# SPI_Interface.net
KiCad netlist of a schematic drawn in Altium Designer
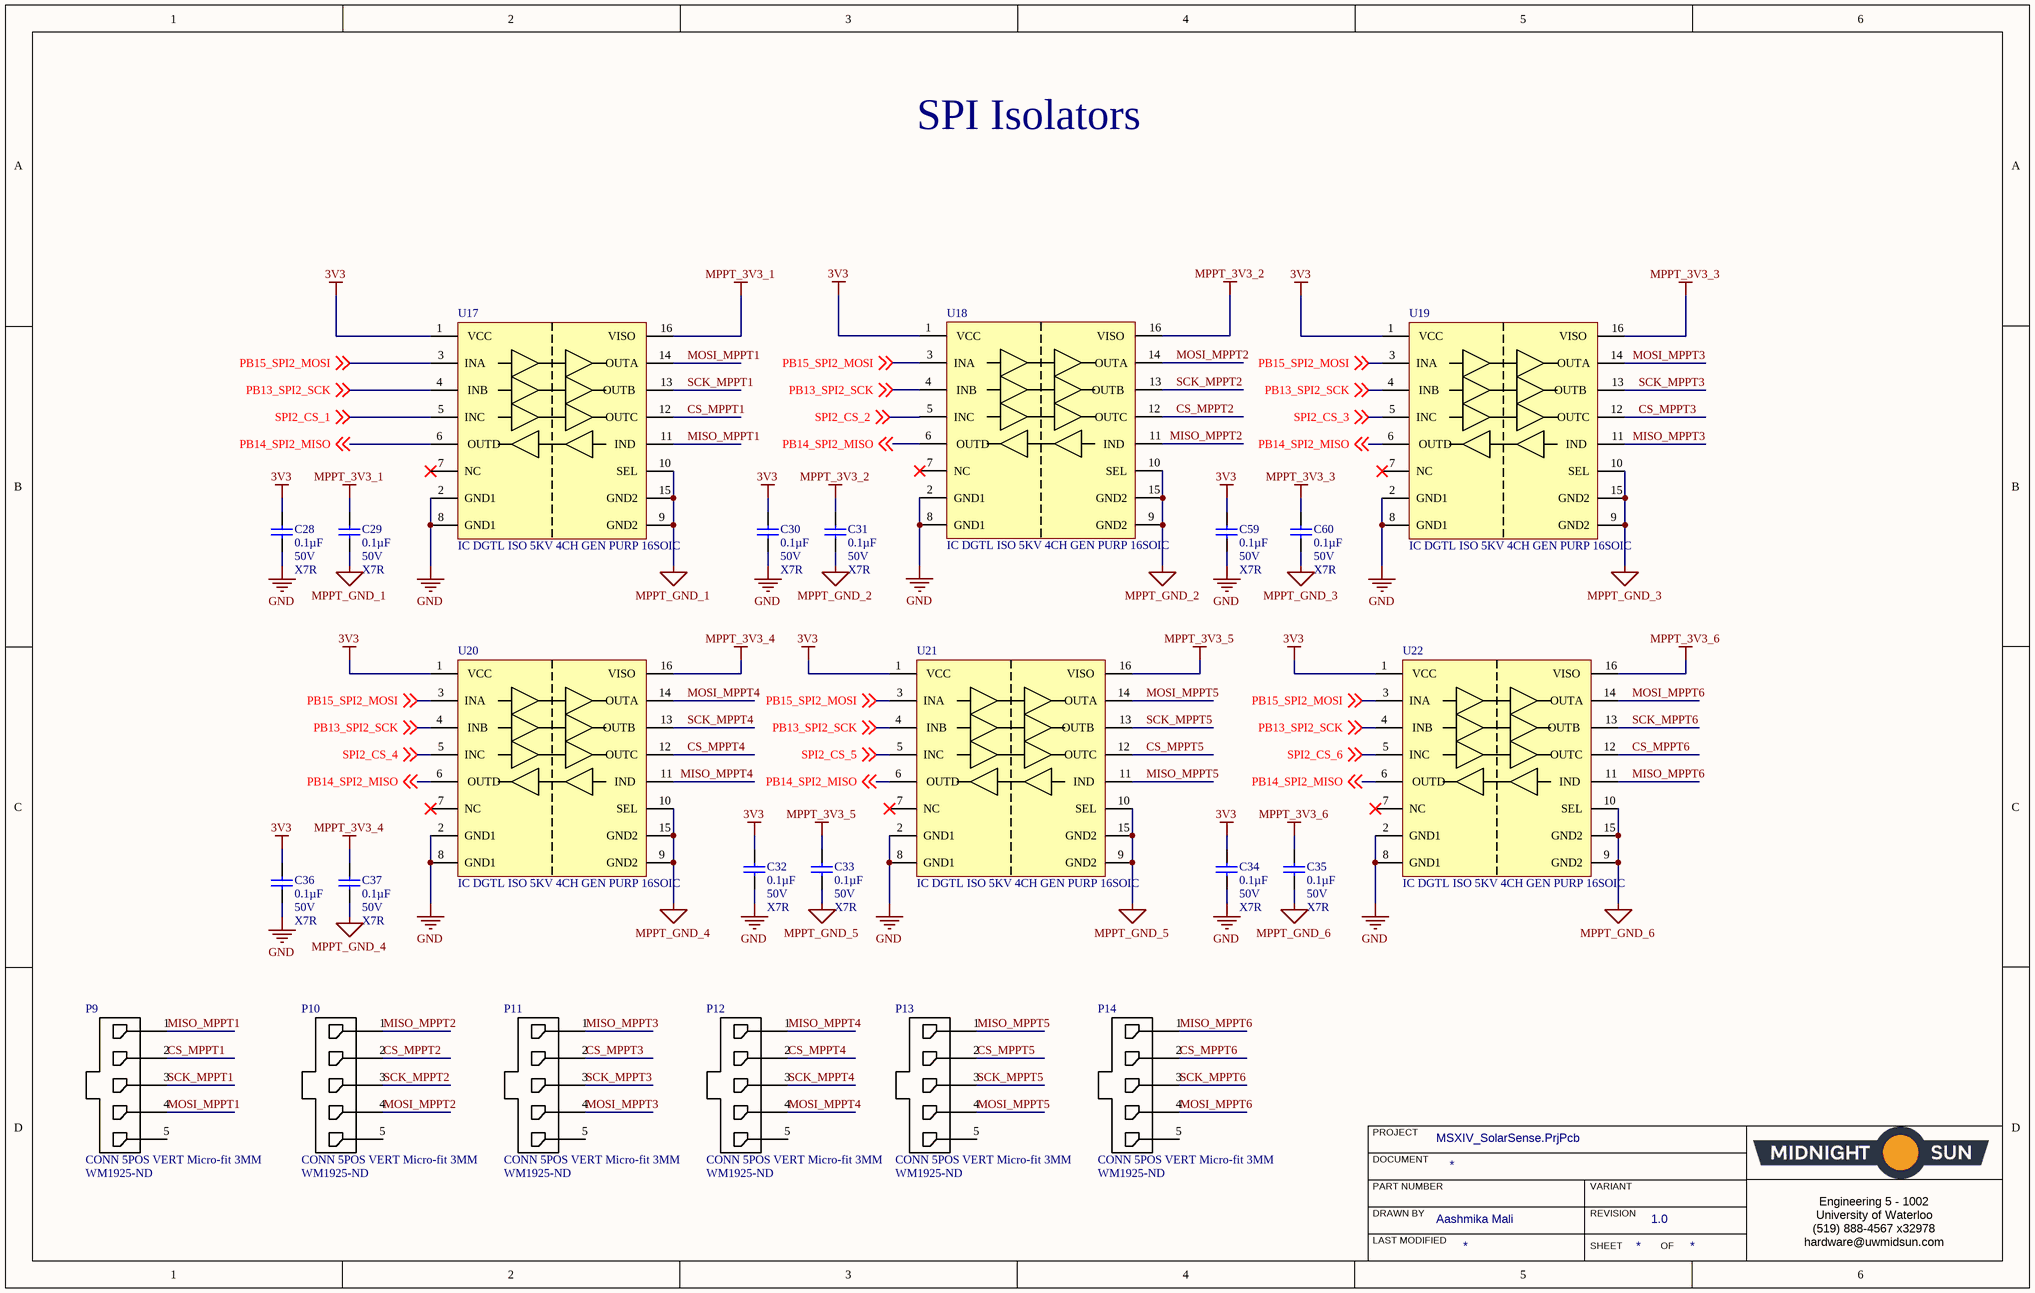
[diagram p0: SPI_Interface.SchDoc]

(export (version "E")
  (design (tool "Eeschema 10.0.6"))
  (components
    (comp (ref "C28")
      (value "CAP CER 0.1UF 50V 10% X7R 0603")
      (footprint "CAP, 0603")
      (description "0.10µF ±10% 50V Ceramic Capacitor X7R 0603 (1608 Metric)")
      (fields
        (field (name "TOLERANCE") "±10%")
        (field (name "CAPACITANCE") "0.1µF")
        (field (name "VOLTAGE") "50V")
        (field (name "TEMPERATURE COEFFICIENT") "X7R")
      )
      (libsource (lib "Schematic Diagrams") (part "CAP CER 0.1UF 50V 10% X7R 0603"))
    )
    (comp (ref "C29")
      (value "CAP CER 0.1UF 50V 10% X7R 0603")
      (footprint "CAP, 0603")
      (description "0.10µF ±10% 50V Ceramic Capacitor X7R 0603 (1608 Metric)")
      (fields
        (field (name "TOLERANCE") "±10%")
        (field (name "CAPACITANCE") "0.1µF")
        (field (name "VOLTAGE") "50V")
        (field (name "TEMPERATURE COEFFICIENT") "X7R")
      )
      (libsource (lib "Schematic Diagrams") (part "CAP CER 0.1UF 50V 10% X7R 0603"))
    )
    (comp (ref "C30")
      (value "CAP CER 0.1UF 50V 10% X7R 0603")
      (footprint "CAP, 0603")
      (description "0.10µF ±10% 50V Ceramic Capacitor X7R 0603 (1608 Metric)")
      (fields
        (field (name "TOLERANCE") "±10%")
        (field (name "CAPACITANCE") "0.1µF")
        (field (name "VOLTAGE") "50V")
        (field (name "TEMPERATURE COEFFICIENT") "X7R")
      )
      (libsource (lib "Schematic Diagrams") (part "CAP CER 0.1UF 50V 10% X7R 0603"))
    )
    (comp (ref "C31")
      (value "CAP CER 0.1UF 50V 10% X7R 0603")
      (footprint "CAP, 0603")
      (description "0.10µF ±10% 50V Ceramic Capacitor X7R 0603 (1608 Metric)")
      (fields
        (field (name "TOLERANCE") "±10%")
        (field (name "CAPACITANCE") "0.1µF")
        (field (name "VOLTAGE") "50V")
        (field (name "TEMPERATURE COEFFICIENT") "X7R")
      )
      (libsource (lib "Schematic Diagrams") (part "CAP CER 0.1UF 50V 10% X7R 0603"))
    )
    (comp (ref "C32")
      (value "CAP CER 0.1UF 50V 10% X7R 0603")
      (footprint "CAP, 0603")
      (description "0.10µF ±10% 50V Ceramic Capacitor X7R 0603 (1608 Metric)")
      (fields
        (field (name "TOLERANCE") "±10%")
        (field (name "CAPACITANCE") "0.1µF")
        (field (name "VOLTAGE") "50V")
        (field (name "TEMPERATURE COEFFICIENT") "X7R")
      )
      (libsource (lib "Schematic Diagrams") (part "CAP CER 0.1UF 50V 10% X7R 0603"))
    )
    (comp (ref "C33")
      (value "CAP CER 0.1UF 50V 10% X7R 0603")
      (footprint "CAP, 0603")
      (description "0.10µF ±10% 50V Ceramic Capacitor X7R 0603 (1608 Metric)")
      (fields
        (field (name "TOLERANCE") "±10%")
        (field (name "CAPACITANCE") "0.1µF")
        (field (name "VOLTAGE") "50V")
        (field (name "TEMPERATURE COEFFICIENT") "X7R")
      )
      (libsource (lib "Schematic Diagrams") (part "CAP CER 0.1UF 50V 10% X7R 0603"))
    )
    (comp (ref "C34")
      (value "CAP CER 0.1UF 50V 10% X7R 0603")
      (footprint "CAP, 0603")
      (description "0.10µF ±10% 50V Ceramic Capacitor X7R 0603 (1608 Metric)")
      (fields
        (field (name "TOLERANCE") "±10%")
        (field (name "CAPACITANCE") "0.1µF")
        (field (name "VOLTAGE") "50V")
        (field (name "TEMPERATURE COEFFICIENT") "X7R")
      )
      (libsource (lib "Schematic Diagrams") (part "CAP CER 0.1UF 50V 10% X7R 0603"))
    )
    (comp (ref "C35")
      (value "CAP CER 0.1UF 50V 10% X7R 0603")
      (footprint "CAP, 0603")
      (description "0.10µF ±10% 50V Ceramic Capacitor X7R 0603 (1608 Metric)")
      (fields
        (field (name "TOLERANCE") "±10%")
        (field (name "CAPACITANCE") "0.1µF")
        (field (name "VOLTAGE") "50V")
        (field (name "TEMPERATURE COEFFICIENT") "X7R")
      )
      (libsource (lib "Schematic Diagrams") (part "CAP CER 0.1UF 50V 10% X7R 0603"))
    )
    (comp (ref "C36")
      (value "CAP CER 0.1UF 50V 10% X7R 0603")
      (footprint "CAP, 0603")
      (description "0.10µF ±10% 50V Ceramic Capacitor X7R 0603 (1608 Metric)")
      (fields
        (field (name "TOLERANCE") "±10%")
        (field (name "CAPACITANCE") "0.1µF")
        (field (name "VOLTAGE") "50V")
        (field (name "TEMPERATURE COEFFICIENT") "X7R")
      )
      (libsource (lib "Schematic Diagrams") (part "CAP CER 0.1UF 50V 10% X7R 0603"))
    )
    (comp (ref "C37")
      (value "CAP CER 0.1UF 50V 10% X7R 0603")
      (footprint "CAP, 0603")
      (description "0.10µF ±10% 50V Ceramic Capacitor X7R 0603 (1608 Metric)")
      (fields
        (field (name "TOLERANCE") "±10%")
        (field (name "CAPACITANCE") "0.1µF")
        (field (name "VOLTAGE") "50V")
        (field (name "TEMPERATURE COEFFICIENT") "X7R")
      )
      (libsource (lib "Schematic Diagrams") (part "CAP CER 0.1UF 50V 10% X7R 0603"))
    )
    (comp (ref "C59")
      (value "CAP CER 0.1UF 50V 10% X7R 0603")
      (footprint "CAP, 0603")
      (description "0.10µF ±10% 50V Ceramic Capacitor X7R 0603 (1608 Metric)")
      (fields
        (field (name "TOLERANCE") "±10%")
        (field (name "CAPACITANCE") "0.1µF")
        (field (name "VOLTAGE") "50V")
        (field (name "TEMPERATURE COEFFICIENT") "X7R")
      )
      (libsource (lib "Schematic Diagrams") (part "CAP CER 0.1UF 50V 10% X7R 0603"))
    )
    (comp (ref "C60")
      (value "CAP CER 0.1UF 50V 10% X7R 0603")
      (footprint "CAP, 0603")
      (description "0.10µF ±10% 50V Ceramic Capacitor X7R 0603 (1608 Metric)")
      (fields
        (field (name "TOLERANCE") "±10%")
        (field (name "CAPACITANCE") "0.1µF")
        (field (name "VOLTAGE") "50V")
        (field (name "TEMPERATURE COEFFICIENT") "X7R")
      )
      (libsource (lib "Schematic Diagrams") (part "CAP CER 0.1UF 50V 10% X7R 0603"))
    )
    (comp (ref "P9")
      (value "CONN 5POS VERT Micro-fit 3MM")
      (footprint "CONN, 5POS MICRO-FIT 3mm")
      (description "Conn Power HDR 5 POS 3mm Solder ST Thru-Hole 5 Terminal 1 Port Micro-Fit 3.0™ Tray")
      (fields
        (field (name "MANUFACTURER") "Molex")
        (field (name "MANUFACTURER PART NUMBER") "0436500516")
        (field (name "SUPPLIER PART NUMBER 1") "WM1925-ND")
      )
      (libsource (lib "Schematic Diagrams") (part "CONN 5POS VERT Micro-fit 3MM"))
    )
    (comp (ref "P10")
      (value "CONN 5POS VERT Micro-fit 3MM")
      (footprint "CONN, 5POS MICRO-FIT 3mm")
      (description "Conn Power HDR 5 POS 3mm Solder ST Thru-Hole 5 Terminal 1 Port Micro-Fit 3.0™ Tray")
      (fields
        (field (name "MANUFACTURER") "Molex")
        (field (name "MANUFACTURER PART NUMBER") "0436500516")
        (field (name "SUPPLIER PART NUMBER 1") "WM1925-ND")
      )
      (libsource (lib "Schematic Diagrams") (part "CONN 5POS VERT Micro-fit 3MM"))
    )
    (comp (ref "P11")
      (value "CONN 5POS VERT Micro-fit 3MM")
      (footprint "CONN, 5POS MICRO-FIT 3mm")
      (description "Conn Power HDR 5 POS 3mm Solder ST Thru-Hole 5 Terminal 1 Port Micro-Fit 3.0™ Tray")
      (fields
        (field (name "MANUFACTURER") "Molex")
        (field (name "MANUFACTURER PART NUMBER") "0436500516")
        (field (name "SUPPLIER PART NUMBER 1") "WM1925-ND")
      )
      (libsource (lib "Schematic Diagrams") (part "CONN 5POS VERT Micro-fit 3MM"))
    )
    (comp (ref "P12")
      (value "CONN 5POS VERT Micro-fit 3MM")
      (footprint "CONN, 5POS MICRO-FIT 3mm")
      (description "Conn Power HDR 5 POS 3mm Solder ST Thru-Hole 5 Terminal 1 Port Micro-Fit 3.0™ Tray")
      (fields
        (field (name "MANUFACTURER") "Molex")
        (field (name "MANUFACTURER PART NUMBER") "0436500516")
        (field (name "SUPPLIER PART NUMBER 1") "WM1925-ND")
      )
      (libsource (lib "Schematic Diagrams") (part "CONN 5POS VERT Micro-fit 3MM"))
    )
    (comp (ref "P13")
      (value "CONN 5POS VERT Micro-fit 3MM")
      (footprint "CONN, 5POS MICRO-FIT 3mm")
      (description "Conn Power HDR 5 POS 3mm Solder ST Thru-Hole 5 Terminal 1 Port Micro-Fit 3.0™ Tray")
      (fields
        (field (name "MANUFACTURER") "Molex")
        (field (name "MANUFACTURER PART NUMBER") "0436500516")
        (field (name "SUPPLIER PART NUMBER 1") "WM1925-ND")
      )
      (libsource (lib "Schematic Diagrams") (part "CONN 5POS VERT Micro-fit 3MM"))
    )
    (comp (ref "P14")
      (value "CONN 5POS VERT Micro-fit 3MM")
      (footprint "CONN, 5POS MICRO-FIT 3mm")
      (description "Conn Power HDR 5 POS 3mm Solder ST Thru-Hole 5 Terminal 1 Port Micro-Fit 3.0™ Tray")
      (fields
        (field (name "MANUFACTURER") "Molex")
        (field (name "MANUFACTURER PART NUMBER") "0436500516")
        (field (name "SUPPLIER PART NUMBER 1") "WM1925-ND")
      )
      (libsource (lib "Schematic Diagrams") (part "CONN 5POS VERT Micro-fit 3MM"))
    )
    (comp (ref "U17")
      (value "IC DGTL ISO 5KV 4CH GEN PURP 16SOIC")
      (footprint "ISOW7841FDWER SOIC-16")
      (libsource (lib "Schematic Diagrams") (part "IC DGTL ISO 5KV 4CH GEN PURP 16SOIC"))
    )
    (comp (ref "U18")
      (value "IC DGTL ISO 5KV 4CH GEN PURP 16SOIC")
      (footprint "ISOW7841FDWER SOIC-16")
      (libsource (lib "Schematic Diagrams") (part "IC DGTL ISO 5KV 4CH GEN PURP 16SOIC"))
    )
    (comp (ref "U19")
      (value "IC DGTL ISO 5KV 4CH GEN PURP 16SOIC")
      (footprint "ISOW7841FDWER SOIC-16")
      (libsource (lib "Schematic Diagrams") (part "IC DGTL ISO 5KV 4CH GEN PURP 16SOIC"))
    )
    (comp (ref "U20")
      (value "IC DGTL ISO 5KV 4CH GEN PURP 16SOIC")
      (footprint "ISOW7841FDWER SOIC-16")
      (libsource (lib "Schematic Diagrams") (part "IC DGTL ISO 5KV 4CH GEN PURP 16SOIC"))
    )
    (comp (ref "U21")
      (value "IC DGTL ISO 5KV 4CH GEN PURP 16SOIC")
      (footprint "ISOW7841FDWER SOIC-16")
      (libsource (lib "Schematic Diagrams") (part "IC DGTL ISO 5KV 4CH GEN PURP 16SOIC"))
    )
    (comp (ref "U22")
      (value "IC DGTL ISO 5KV 4CH GEN PURP 16SOIC")
      (footprint "ISOW7841FDWER SOIC-16")
      (libsource (lib "Schematic Diagrams") (part "IC DGTL ISO 5KV 4CH GEN PURP 16SOIC"))
    )
  )
  (nets
    (net (code "1") (name "/CS_MPPT1") (class "Default")
      (node (ref "P9") (pin "2") (pinfunction "2_2") (pintype "passive"))
      (node (ref "U17") (pin "12") (pinfunction "OUTC_12") (pintype "passive"))
    )
    (net (code "2") (name "/CS_MPPT2") (class "Default")
      (node (ref "P10") (pin "2") (pinfunction "2_2") (pintype "passive"))
      (node (ref "U18") (pin "12") (pinfunction "OUTC_12") (pintype "passive"))
    )
    (net (code "3") (name "/CS_MPPT3") (class "Default")
      (node (ref "P11") (pin "2") (pinfunction "2_2") (pintype "passive"))
      (node (ref "U19") (pin "12") (pinfunction "OUTC_12") (pintype "passive"))
    )
    (net (code "4") (name "/CS_MPPT4") (class "Default")
      (node (ref "P12") (pin "2") (pinfunction "2_2") (pintype "passive"))
      (node (ref "U20") (pin "12") (pinfunction "OUTC_12") (pintype "passive"))
    )
    (net (code "5") (name "/CS_MPPT5") (class "Default")
      (node (ref "P13") (pin "2") (pinfunction "2_2") (pintype "passive"))
      (node (ref "U21") (pin "12") (pinfunction "OUTC_12") (pintype "passive"))
    )
    (net (code "6") (name "/CS_MPPT6") (class "Default")
      (node (ref "P14") (pin "2") (pinfunction "2_2") (pintype "passive"))
      (node (ref "U22") (pin "12") (pinfunction "OUTC_12") (pintype "passive"))
    )
    (net (code "7") (name "/MISO_MPPT1") (class "Default")
      (node (ref "P9") (pin "1") (pinfunction "1_1") (pintype "passive"))
      (node (ref "U17") (pin "11") (pinfunction "IND_11") (pintype "passive"))
    )
    (net (code "8") (name "/MISO_MPPT2") (class "Default")
      (node (ref "P10") (pin "1") (pinfunction "1_1") (pintype "passive"))
      (node (ref "U18") (pin "11") (pinfunction "IND_11") (pintype "passive"))
    )
    (net (code "9") (name "/MISO_MPPT3") (class "Default")
      (node (ref "P11") (pin "1") (pinfunction "1_1") (pintype "passive"))
      (node (ref "U19") (pin "11") (pinfunction "IND_11") (pintype "passive"))
    )
    (net (code "10") (name "/MISO_MPPT4") (class "Default")
      (node (ref "P12") (pin "1") (pinfunction "1_1") (pintype "passive"))
      (node (ref "U20") (pin "11") (pinfunction "IND_11") (pintype "passive"))
    )
    (net (code "11") (name "/MISO_MPPT5") (class "Default")
      (node (ref "P13") (pin "1") (pinfunction "1_1") (pintype "passive"))
      (node (ref "U21") (pin "11") (pinfunction "IND_11") (pintype "passive"))
    )
    (net (code "12") (name "/MISO_MPPT6") (class "Default")
      (node (ref "P14") (pin "1") (pinfunction "1_1") (pintype "passive"))
      (node (ref "U22") (pin "11") (pinfunction "IND_11") (pintype "passive"))
    )
    (net (code "13") (name "/MOSI_MPPT1") (class "Default")
      (node (ref "P9") (pin "4") (pinfunction "4_4") (pintype "passive"))
      (node (ref "U17") (pin "14") (pinfunction "OUTA_14") (pintype "passive"))
    )
    (net (code "14") (name "/MOSI_MPPT2") (class "Default")
      (node (ref "P10") (pin "4") (pinfunction "4_4") (pintype "passive"))
      (node (ref "U18") (pin "14") (pinfunction "OUTA_14") (pintype "passive"))
    )
    (net (code "15") (name "/MOSI_MPPT3") (class "Default")
      (node (ref "P11") (pin "4") (pinfunction "4_4") (pintype "passive"))
      (node (ref "U19") (pin "14") (pinfunction "OUTA_14") (pintype "passive"))
    )
    (net (code "16") (name "/MOSI_MPPT4") (class "Default")
      (node (ref "P12") (pin "4") (pinfunction "4_4") (pintype "passive"))
      (node (ref "U20") (pin "14") (pinfunction "OUTA_14") (pintype "passive"))
    )
    (net (code "17") (name "/MOSI_MPPT5") (class "Default")
      (node (ref "P13") (pin "4") (pinfunction "4_4") (pintype "passive"))
      (node (ref "U21") (pin "14") (pinfunction "OUTA_14") (pintype "passive"))
    )
    (net (code "18") (name "/MOSI_MPPT6") (class "Default")
      (node (ref "P14") (pin "4") (pinfunction "4_4") (pintype "passive"))
      (node (ref "U22") (pin "14") (pinfunction "OUTA_14") (pintype "passive"))
    )
    (net (code "19") (name "/SCK_MPPT1") (class "Default")
      (node (ref "P9") (pin "3") (pinfunction "3_3") (pintype "passive"))
      (node (ref "U17") (pin "13") (pinfunction "OUTB_13") (pintype "passive"))
    )
    (net (code "20") (name "/SCK_MPPT2") (class "Default")
      (node (ref "P10") (pin "3") (pinfunction "3_3") (pintype "passive"))
      (node (ref "U18") (pin "13") (pinfunction "OUTB_13") (pintype "passive"))
    )
    (net (code "21") (name "/SCK_MPPT3") (class "Default")
      (node (ref "P11") (pin "3") (pinfunction "3_3") (pintype "passive"))
      (node (ref "U19") (pin "13") (pinfunction "OUTB_13") (pintype "passive"))
    )
    (net (code "22") (name "/SCK_MPPT4") (class "Default")
      (node (ref "P12") (pin "3") (pinfunction "3_3") (pintype "passive"))
      (node (ref "U20") (pin "13") (pinfunction "OUTB_13") (pintype "passive"))
    )
    (net (code "23") (name "/SCK_MPPT5") (class "Default")
      (node (ref "P13") (pin "3") (pinfunction "3_3") (pintype "passive"))
      (node (ref "U21") (pin "13") (pinfunction "OUTB_13") (pintype "passive"))
    )
    (net (code "24") (name "/SCK_MPPT6") (class "Default")
      (node (ref "P14") (pin "3") (pinfunction "3_3") (pintype "passive"))
      (node (ref "U22") (pin "13") (pinfunction "OUTB_13") (pintype "passive"))
    )
    (net (code "25") (name "3V3") (class "Default")
      (node (ref "C28") (pin "1") (pinfunction "1_1") (pintype "passive"))
      (node (ref "C30") (pin "1") (pinfunction "1_1") (pintype "passive"))
      (node (ref "C32") (pin "1") (pinfunction "1_1") (pintype "passive"))
      (node (ref "C34") (pin "1") (pinfunction "1_1") (pintype "passive"))
      (node (ref "C36") (pin "1") (pinfunction "1_1") (pintype "passive"))
      (node (ref "C59") (pin "1") (pinfunction "1_1") (pintype "passive"))
      (node (ref "U17") (pin "1") (pinfunction "VCC_1") (pintype "power_in"))
      (node (ref "U18") (pin "1") (pinfunction "VCC_1") (pintype "power_in"))
      (node (ref "U19") (pin "1") (pinfunction "VCC_1") (pintype "power_in"))
      (node (ref "U20") (pin "1") (pinfunction "VCC_1") (pintype "power_in"))
      (node (ref "U21") (pin "1") (pinfunction "VCC_1") (pintype "power_in"))
      (node (ref "U22") (pin "1") (pinfunction "VCC_1") (pintype "power_in"))
    )
    (net (code "26") (name "GND") (class "Default")
      (node (ref "C28") (pin "2") (pinfunction "2_2") (pintype "passive"))
      (node (ref "C30") (pin "2") (pinfunction "2_2") (pintype "passive"))
      (node (ref "C32") (pin "2") (pinfunction "2_2") (pintype "passive"))
      (node (ref "C34") (pin "2") (pinfunction "2_2") (pintype "passive"))
      (node (ref "C36") (pin "2") (pinfunction "2_2") (pintype "passive"))
      (node (ref "C59") (pin "2") (pinfunction "2_2") (pintype "passive"))
      (node (ref "U17") (pin "2") (pinfunction "GND1_2") (pintype "passive"))
      (node (ref "U17") (pin "8") (pinfunction "GND1_8") (pintype "passive"))
      (node (ref "U18") (pin "2") (pinfunction "GND1_2") (pintype "passive"))
      (node (ref "U18") (pin "8") (pinfunction "GND1_8") (pintype "passive"))
      (node (ref "U19") (pin "2") (pinfunction "GND1_2") (pintype "passive"))
      (node (ref "U19") (pin "8") (pinfunction "GND1_8") (pintype "passive"))
      (node (ref "U20") (pin "2") (pinfunction "GND1_2") (pintype "passive"))
      (node (ref "U20") (pin "8") (pinfunction "GND1_8") (pintype "passive"))
      (node (ref "U21") (pin "2") (pinfunction "GND1_2") (pintype "passive"))
      (node (ref "U21") (pin "8") (pinfunction "GND1_8") (pintype "passive"))
      (node (ref "U22") (pin "2") (pinfunction "GND1_2") (pintype "passive"))
      (node (ref "U22") (pin "8") (pinfunction "GND1_8") (pintype "passive"))
    )
    (net (code "27") (name "MPPT_3V3_1") (class "Default")
      (node (ref "C29") (pin "1") (pinfunction "1_1") (pintype "passive"))
      (node (ref "U17") (pin "16") (pinfunction "VISO_16") (pintype "power_in"))
    )
    (net (code "28") (name "MPPT_3V3_2") (class "Default")
      (node (ref "C31") (pin "1") (pinfunction "1_1") (pintype "passive"))
      (node (ref "U18") (pin "16") (pinfunction "VISO_16") (pintype "power_in"))
    )
    (net (code "29") (name "MPPT_3V3_3") (class "Default")
      (node (ref "C60") (pin "1") (pinfunction "1_1") (pintype "passive"))
      (node (ref "U19") (pin "16") (pinfunction "VISO_16") (pintype "power_in"))
    )
    (net (code "30") (name "MPPT_3V3_4") (class "Default")
      (node (ref "C37") (pin "1") (pinfunction "1_1") (pintype "passive"))
      (node (ref "U20") (pin "16") (pinfunction "VISO_16") (pintype "power_in"))
    )
    (net (code "31") (name "MPPT_3V3_5") (class "Default")
      (node (ref "C33") (pin "1") (pinfunction "1_1") (pintype "passive"))
      (node (ref "U21") (pin "16") (pinfunction "VISO_16") (pintype "power_in"))
    )
    (net (code "32") (name "MPPT_3V3_6") (class "Default")
      (node (ref "C35") (pin "1") (pinfunction "1_1") (pintype "passive"))
      (node (ref "U22") (pin "16") (pinfunction "VISO_16") (pintype "power_in"))
    )
    (net (code "33") (name "MPPT_GND_1") (class "Default")
      (node (ref "C29") (pin "2") (pinfunction "2_2") (pintype "passive"))
      (node (ref "U17") (pin "10") (pinfunction "SEL_10") (pintype "passive"))
      (node (ref "U17") (pin "15") (pinfunction "GND2_15") (pintype "passive"))
      (node (ref "U17") (pin "9") (pinfunction "GND2_9") (pintype "passive"))
    )
    (net (code "34") (name "MPPT_GND_2") (class "Default")
      (node (ref "C31") (pin "2") (pinfunction "2_2") (pintype "passive"))
      (node (ref "U18") (pin "10") (pinfunction "SEL_10") (pintype "passive"))
      (node (ref "U18") (pin "15") (pinfunction "GND2_15") (pintype "passive"))
      (node (ref "U18") (pin "9") (pinfunction "GND2_9") (pintype "passive"))
    )
    (net (code "35") (name "MPPT_GND_3") (class "Default")
      (node (ref "C60") (pin "2") (pinfunction "2_2") (pintype "passive"))
      (node (ref "U19") (pin "10") (pinfunction "SEL_10") (pintype "passive"))
      (node (ref "U19") (pin "15") (pinfunction "GND2_15") (pintype "passive"))
      (node (ref "U19") (pin "9") (pinfunction "GND2_9") (pintype "passive"))
    )
    (net (code "36") (name "MPPT_GND_4") (class "Default")
      (node (ref "C37") (pin "2") (pinfunction "2_2") (pintype "passive"))
      (node (ref "U20") (pin "10") (pinfunction "SEL_10") (pintype "passive"))
      (node (ref "U20") (pin "15") (pinfunction "GND2_15") (pintype "passive"))
      (node (ref "U20") (pin "9") (pinfunction "GND2_9") (pintype "passive"))
    )
    (net (code "37") (name "MPPT_GND_5") (class "Default")
      (node (ref "C33") (pin "2") (pinfunction "2_2") (pintype "passive"))
      (node (ref "U21") (pin "10") (pinfunction "SEL_10") (pintype "passive"))
      (node (ref "U21") (pin "15") (pinfunction "GND2_15") (pintype "passive"))
      (node (ref "U21") (pin "9") (pinfunction "GND2_9") (pintype "passive"))
    )
    (net (code "38") (name "MPPT_GND_6") (class "Default")
      (node (ref "C35") (pin "2") (pinfunction "2_2") (pintype "passive"))
      (node (ref "U22") (pin "10") (pinfunction "SEL_10") (pintype "passive"))
      (node (ref "U22") (pin "15") (pinfunction "GND2_15") (pintype "passive"))
      (node (ref "U22") (pin "9") (pinfunction "GND2_9") (pintype "passive"))
    )
    (net (code "39") (name "PB13_SPI2_SCK") (class "Default")
      (node (ref "U17") (pin "4") (pinfunction "INB_4") (pintype "passive"))
      (node (ref "U18") (pin "4") (pinfunction "INB_4") (pintype "passive"))
      (node (ref "U19") (pin "4") (pinfunction "INB_4") (pintype "passive"))
      (node (ref "U20") (pin "4") (pinfunction "INB_4") (pintype "passive"))
      (node (ref "U21") (pin "4") (pinfunction "INB_4") (pintype "passive"))
      (node (ref "U22") (pin "4") (pinfunction "INB_4") (pintype "passive"))
    )
    (net (code "40") (name "PB14_SPI2_MISO") (class "Default")
      (node (ref "U17") (pin "6") (pinfunction "OUTD_6") (pintype "passive"))
      (node (ref "U18") (pin "6") (pinfunction "OUTD_6") (pintype "passive"))
      (node (ref "U19") (pin "6") (pinfunction "OUTD_6") (pintype "passive"))
      (node (ref "U20") (pin "6") (pinfunction "OUTD_6") (pintype "passive"))
      (node (ref "U21") (pin "6") (pinfunction "OUTD_6") (pintype "passive"))
      (node (ref "U22") (pin "6") (pinfunction "OUTD_6") (pintype "passive"))
    )
    (net (code "41") (name "PB15_SPI2_MOSI") (class "Default")
      (node (ref "U17") (pin "3") (pinfunction "INA_3") (pintype "passive"))
      (node (ref "U18") (pin "3") (pinfunction "INA_3") (pintype "passive"))
      (node (ref "U19") (pin "3") (pinfunction "INA_3") (pintype "passive"))
      (node (ref "U20") (pin "3") (pinfunction "INA_3") (pintype "passive"))
      (node (ref "U21") (pin "3") (pinfunction "INA_3") (pintype "passive"))
      (node (ref "U22") (pin "3") (pinfunction "INA_3") (pintype "passive"))
    )
    (net (code "42") (name "SPI2_CS_1") (class "Default")
      (node (ref "U17") (pin "5") (pinfunction "INC_5") (pintype "passive"))
    )
    (net (code "43") (name "SPI2_CS_2") (class "Default")
      (node (ref "U18") (pin "5") (pinfunction "INC_5") (pintype "passive"))
    )
    (net (code "44") (name "SPI2_CS_3") (class "Default")
      (node (ref "U19") (pin "5") (pinfunction "INC_5") (pintype "passive"))
    )
    (net (code "45") (name "SPI2_CS_4") (class "Default")
      (node (ref "U20") (pin "5") (pinfunction "INC_5") (pintype "passive"))
    )
    (net (code "46") (name "SPI2_CS_5") (class "Default")
      (node (ref "U21") (pin "5") (pinfunction "INC_5") (pintype "passive"))
    )
    (net (code "47") (name "SPI2_CS_6") (class "Default")
      (node (ref "U22") (pin "5") (pinfunction "INC_5") (pintype "passive"))
    )
    (net (code "48") (name "unconnected-(P9-Pad5)") (class "Default")
      (node (ref "P9") (pin "5") (pinfunction "5_5") (pintype "passive"))
    )
    (net (code "49") (name "unconnected-(P10-Pad5)") (class "Default")
      (node (ref "P10") (pin "5") (pinfunction "5_5") (pintype "passive"))
    )
    (net (code "50") (name "unconnected-(P11-Pad5)") (class "Default")
      (node (ref "P11") (pin "5") (pinfunction "5_5") (pintype "passive"))
    )
    (net (code "51") (name "unconnected-(P12-Pad5)") (class "Default")
      (node (ref "P12") (pin "5") (pinfunction "5_5") (pintype "passive"))
    )
    (net (code "52") (name "unconnected-(P13-Pad5)") (class "Default")
      (node (ref "P13") (pin "5") (pinfunction "5_5") (pintype "passive"))
    )
    (net (code "53") (name "unconnected-(P14-Pad5)") (class "Default")
      (node (ref "P14") (pin "5") (pinfunction "5_5") (pintype "passive"))
    )
    (net (code "54") (name "unconnected-(U17-NC-Pad7)") (class "Default")
      (node (ref "U17") (pin "7") (pinfunction "NC_7") (pintype "passive+no_connect"))
    )
    (net (code "55") (name "unconnected-(U18-NC-Pad7)") (class "Default")
      (node (ref "U18") (pin "7") (pinfunction "NC_7") (pintype "passive+no_connect"))
    )
    (net (code "56") (name "unconnected-(U19-NC-Pad7)") (class "Default")
      (node (ref "U19") (pin "7") (pinfunction "NC_7") (pintype "passive+no_connect"))
    )
    (net (code "57") (name "unconnected-(U20-NC-Pad7)") (class "Default")
      (node (ref "U20") (pin "7") (pinfunction "NC_7") (pintype "passive+no_connect"))
    )
    (net (code "58") (name "unconnected-(U21-NC-Pad7)") (class "Default")
      (node (ref "U21") (pin "7") (pinfunction "NC_7") (pintype "passive+no_connect"))
    )
    (net (code "59") (name "unconnected-(U22-NC-Pad7)") (class "Default")
      (node (ref "U22") (pin "7") (pinfunction "NC_7") (pintype "passive+no_connect"))
    )
  )
)
